# atmega_midi_x0x_heart_groundplane.net
KiCad netlist of a schematic drawn in EAGLE
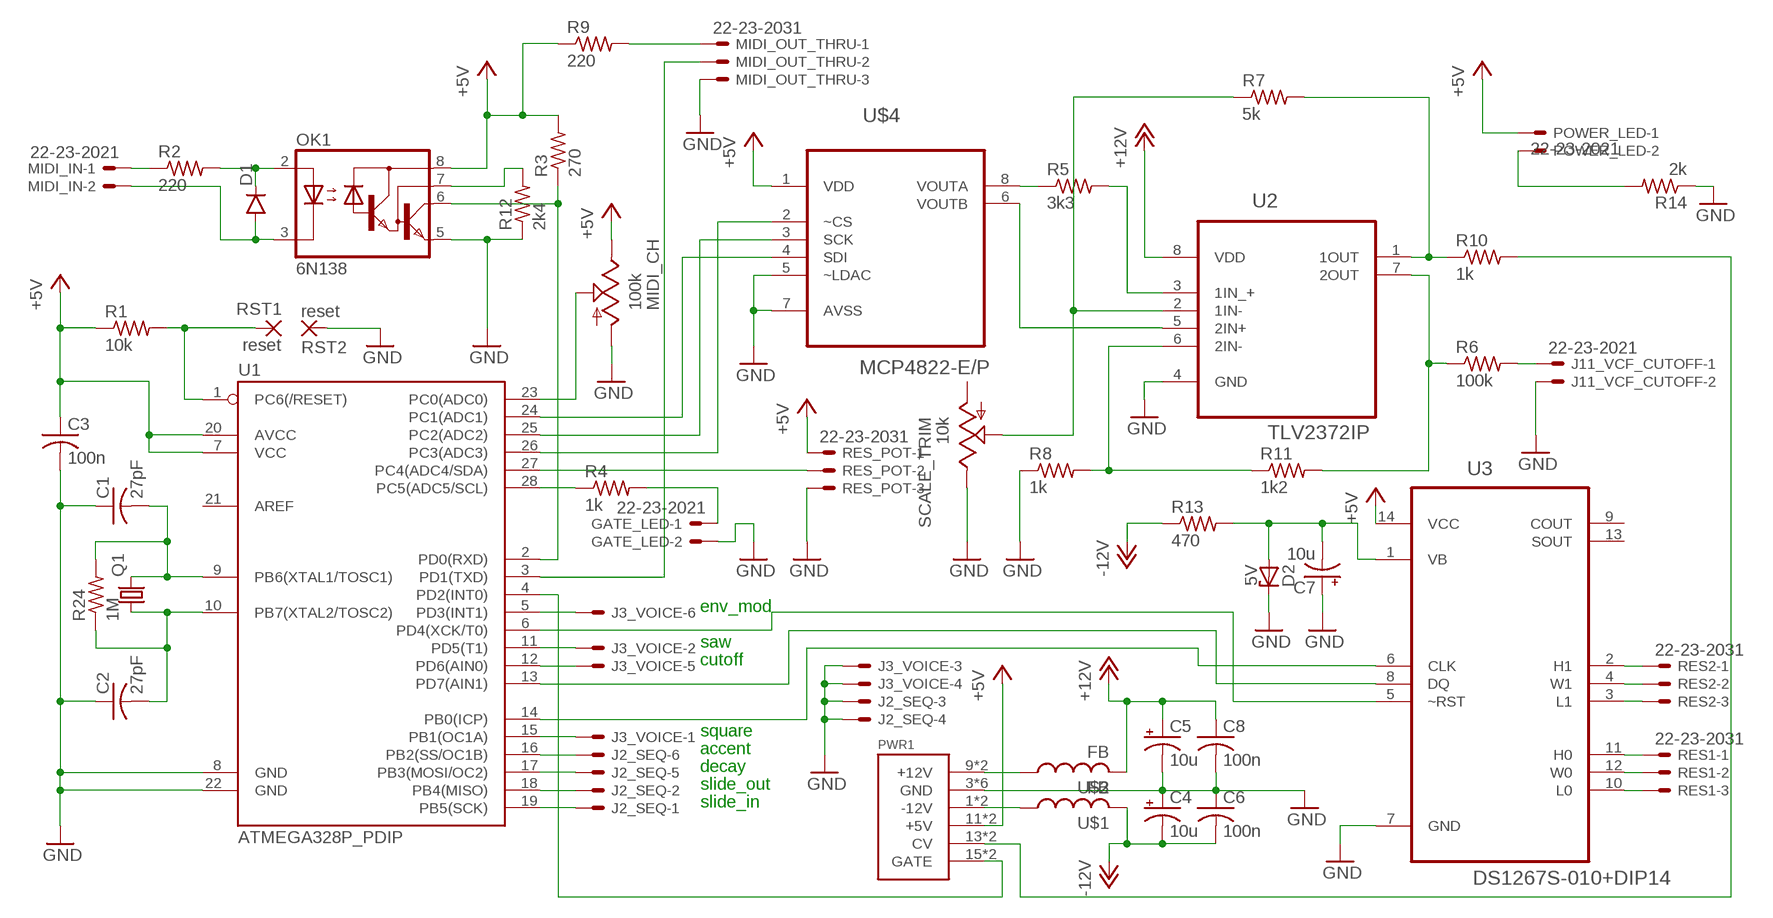
[diagram p0: schematic, sheet 1]

(export (version "E")
  (design (tool "Eeschema 10.0.6"))
  (components
    (comp (ref "C1")
      (value "27pF")
      (footprint "eagle-import:C050-024X044")
      (libsource (lib "eagle-import") (part "C-US050-024X044"))
    )
    (comp (ref "C2")
      (value "27pF")
      (footprint "eagle-import:C050-024X044")
      (libsource (lib "eagle-import") (part "C-US050-024X044"))
    )
    (comp (ref "C3")
      (value "100n")
      (footprint "eagle-import:C050-024X044")
      (libsource (lib "eagle-import") (part "C-US050-024X044"))
    )
    (comp (ref "C4")
      (value "10u")
      (footprint "eagle-import:B45181A")
      (libsource (lib "eagle-import") (part "CPOL-USB45181A"))
    )
    (comp (ref "C5")
      (value "10u")
      (footprint "eagle-import:B45181A")
      (libsource (lib "eagle-import") (part "CPOL-USB45181A"))
    )
    (comp (ref "C6")
      (value "100n")
      (footprint "eagle-import:C050-024X044")
      (libsource (lib "eagle-import") (part "C-US050-024X044"))
    )
    (comp (ref "C7")
      (value "10u")
      (footprint "eagle-import:B45181B")
      (libsource (lib "eagle-import") (part "CPOL-USB45181B"))
    )
    (comp (ref "C8")
      (value "100n")
      (footprint "eagle-import:C050-024X044")
      (libsource (lib "eagle-import") (part "C-US050-024X044"))
    )
    (comp (ref "D1")
      (value "DIODE1N4148")
      (footprint "eagle-import:DIODE-1N4148")
      (libsource (lib "eagle-import") (part "DIODE1N4148"))
    )
    (comp (ref "D2")
      (value "5V")
      (footprint "eagle-import:DO35Z10")
      (libsource (lib "eagle-import") (part "ZENER-DIODEDO35Z10"))
    )
    (comp (ref "GATE_LED")
      (value "22-23-2021")
      (footprint "eagle-import:22-23-2021")
      (fields (field (name "MF") "MOLEX"))
      (libsource (lib "eagle-import") (part "22-23-2021"))
    )
    (comp (ref "J2_SEQ")
      (value "22-23-2061")
      (footprint "eagle-import:22-23-2061")
      (fields (field (name "MF") "MOLEX"))
      (libsource (lib "eagle-import") (part "22-23-2061"))
    )
    (comp (ref "J3_VOICE")
      (value "22-23-2061")
      (footprint "eagle-import:22-23-2061")
      (fields (field (name "MF") "MOLEX"))
      (libsource (lib "eagle-import") (part "22-23-2061"))
    )
    (comp (ref "J11_VCF_CUTOFF")
      (value "22-23-2021")
      (footprint "eagle-import:22-23-2021")
      (fields (field (name "MF") "MOLEX"))
      (libsource (lib "eagle-import") (part "22-23-2021"))
    )
    (comp (ref "MIDI_CH")
      (value "100k")
      (footprint "eagle-import:B64W")
      (libsource (lib "eagle-import") (part "TRIM_US-B64W"))
    )
    (comp (ref "MIDI_IN")
      (value "22-23-2021")
      (footprint "eagle-import:22-23-2021")
      (fields (field (name "MF") "MOLEX"))
      (libsource (lib "eagle-import") (part "22-23-2021"))
    )
    (comp (ref "MIDI_OUT_THRU")
      (value "22-23-2031")
      (footprint "eagle-import:22-23-2031")
      (fields (field (name "MF") "MOLEX"))
      (libsource (lib "eagle-import") (part "22-23-2031"))
    )
    (comp (ref "OK1")
      (value "6N138")
      (footprint "eagle-import:DIL08")
      (fields (field (name "MF") "VISHAY/TELEFUNKEN"))
      (libsource (lib "eagle-import") (part "6N138"))
    )
    (comp (ref "POWER_LED")
      (value "22-23-2021")
      (footprint "eagle-import:22-23-2021")
      (fields (field (name "MF") "MOLEX"))
      (libsource (lib "eagle-import") (part "22-23-2021"))
    )
    (comp (ref "PWR1")
      (value "POWER")
      (footprint "eagle-import:POWER_16")
      (libsource (lib "eagle-import") (part "POWER"))
    )
    (comp (ref "Q1")
      (value "CRYSTALHC49S")
      (footprint "eagle-import:HC49_S")
      (libsource (lib "eagle-import") (part "CRYSTALHC49S"))
    )
    (comp (ref "R1")
      (value "10k")
      (footprint "eagle-import:0207_10")
      (libsource (lib "eagle-import") (part "R-US_0207/10"))
    )
    (comp (ref "R2")
      (value "220")
      (footprint "eagle-import:0207_10")
      (libsource (lib "eagle-import") (part "R-US_0207/10"))
    )
    (comp (ref "R3")
      (value "270")
      (footprint "eagle-import:0207_10")
      (libsource (lib "eagle-import") (part "R-US_0207/10"))
    )
    (comp (ref "R4")
      (value "1k")
      (footprint "eagle-import:0207_10")
      (libsource (lib "eagle-import") (part "R-US_0207/10"))
    )
    (comp (ref "R5")
      (value "3k3")
      (footprint "eagle-import:0207_10")
      (libsource (lib "eagle-import") (part "R-US_0207/10"))
    )
    (comp (ref "R6")
      (value "100k")
      (footprint "eagle-import:0207_10")
      (libsource (lib "eagle-import") (part "R-US_0207/10"))
    )
    (comp (ref "R7")
      (value "5k")
      (footprint "eagle-import:0207_10")
      (libsource (lib "eagle-import") (part "R-US_0207/10"))
    )
    (comp (ref "R8")
      (value "1k")
      (footprint "eagle-import:0207_10")
      (libsource (lib "eagle-import") (part "R-US_0207/10"))
    )
    (comp (ref "R9")
      (value "220")
      (footprint "eagle-import:0207_10")
      (libsource (lib "eagle-import") (part "R-US_0207/10"))
    )
    (comp (ref "R10")
      (value "1k")
      (footprint "eagle-import:0207_10")
      (libsource (lib "eagle-import") (part "R-US_0207/10"))
    )
    (comp (ref "R11")
      (value "1k2")
      (footprint "eagle-import:0207_10")
      (libsource (lib "eagle-import") (part "R-US_0207/10"))
    )
    (comp (ref "R12")
      (value "2k4")
      (footprint "eagle-import:0207_10")
      (libsource (lib "eagle-import") (part "R-US_0207/10"))
    )
    (comp (ref "R13")
      (value "470")
      (footprint "eagle-import:0207_10")
      (libsource (lib "eagle-import") (part "R-US_0207/10"))
    )
    (comp (ref "R14")
      (value "2k")
      (footprint "eagle-import:0207_10")
      (libsource (lib "eagle-import") (part "R-US_0207/10"))
    )
    (comp (ref "R24")
      (value "1M")
      (footprint "eagle-import:0207_10")
      (libsource (lib "eagle-import") (part "R-US_0207/10"))
    )
    (comp (ref "RES1")
      (value "22-23-2031")
      (footprint "eagle-import:22-23-2031")
      (fields (field (name "MF") "MOLEX"))
      (libsource (lib "eagle-import") (part "22-23-2031"))
    )
    (comp (ref "RES2")
      (value "22-23-2031")
      (footprint "eagle-import:22-23-2031")
      (fields (field (name "MF") "MOLEX"))
      (libsource (lib "eagle-import") (part "22-23-2031"))
    )
    (comp (ref "RES_POT")
      (value "22-23-2031")
      (footprint "eagle-import:22-23-2031")
      (fields (field (name "MF") "MOLEX"))
      (libsource (lib "eagle-import") (part "22-23-2031"))
    )
    (comp (ref "RST1")
      (value "reset")
      (footprint "eagle-import:2,54_0,9")
      (libsource (lib "eagle-import") (part "2,54/0,9"))
    )
    (comp (ref "RST2")
      (value "reset")
      (footprint "eagle-import:2,54_0,9")
      (libsource (lib "eagle-import") (part "2,54/0,9"))
    )
    (comp (ref "SCALE_TRIM")
      (value "10k")
      (footprint "eagle-import:B64W")
      (libsource (lib "eagle-import") (part "TRIM_US-B64W"))
    )
    (comp (ref "U$1") (value "FB") (footprint "eagle-import:FB") (libsource (lib "eagle-import") (part "FB")))
    (comp (ref "U$2") (value "FB") (footprint "eagle-import:FB") (libsource (lib "eagle-import") (part "FB")))
    (comp (ref "U$4")
      (value "MCP4822-E/P")
      (footprint "eagle-import:DIP254P762X432-8")
      (libsource (lib "eagle-import") (part "MCP4822-E/P"))
    )
    (comp (ref "U1")
      (value "ATMEGA328P_PDIP")
      (footprint "eagle-import:DIL28-3")
      (libsource (lib "eagle-import") (part "ATMEGA328P_PDIP"))
    )
    (comp (ref "U2")
      (value "TLV2372IP")
      (footprint "eagle-import:DIP254P762X508-8")
      (libsource (lib "eagle-import") (part "TLV2372IP"))
    )
    (comp (ref "U3")
      (value "DS1267S-010+DIP14")
      (footprint "eagle-import:DIP14")
      (libsource (lib "eagle-import") (part "DS1267S-010+DIP14"))
    )
  )
  (nets
    (net (code "1") (name "+5V") (class "Default")
      (node (ref "C3") (pin "1") (pinfunction "1_1") (pintype "passive"))
      (node (ref "MIDI_CH") (pin "E") (pinfunction "E_E") (pintype "passive"))
      (node (ref "OK1") (pin "8") (pinfunction "VCC_8") (pintype "passive"))
      (node (ref "POWER_LED") (pin "1") (pinfunction "S_1") (pintype "passive"))
      (node (ref "PWR1") (pin "11") (pinfunction "+5V_11") (pintype "bidirectional"))
      (node (ref "PWR1") (pin "12") (pinfunction "+5V_12") (pintype "bidirectional"))
      (node (ref "R1") (pin "1") (pinfunction "1_1") (pintype "passive"))
      (node (ref "R3") (pin "2") (pinfunction "2_2") (pintype "passive"))
      (node (ref "R9") (pin "1") (pinfunction "1_1") (pintype "passive"))
      (node (ref "RES_POT") (pin "1") (pinfunction "S_1") (pintype "passive"))
      (node (ref "U$4") (pin "1") (pinfunction "VDD_1") (pintype "power_in"))
      (node (ref "U1") (pin "20") (pinfunction "AVCC_20") (pintype "bidirectional"))
      (node (ref "U1") (pin "7") (pinfunction "VCC_7") (pintype "bidirectional"))
      (node (ref "U3") (pin "14") (pinfunction "VCC_14") (pintype "power_in"))
    )
    (net (code "2") (name "+12V") (class "Default")
      (node (ref "C5") (pin "+") (pinfunction "+_+") (pintype "passive"))
      (node (ref "C8") (pin "1") (pinfunction "1_1") (pintype "passive"))
      (node (ref "U$2") (pin "P$2") (pinfunction "2_P$2") (pintype "passive"))
      (node (ref "U2") (pin "8") (pinfunction "VDD_8") (pintype "power_in"))
    )
    (net (code "3") (name "-12V") (class "Default")
      (node (ref "C4") (pin "-") (pinfunction "-_-") (pintype "passive"))
      (node (ref "C6") (pin "2") (pinfunction "2_2") (pintype "passive"))
      (node (ref "R13") (pin "1") (pinfunction "1_1") (pintype "passive"))
      (node (ref "U$1") (pin "P$2") (pinfunction "2_P$2") (pintype "passive"))
    )
    (net (code "4") (name "GND") (class "Default")
      (node (ref "C1") (pin "1") (pinfunction "1_1") (pintype "passive"))
      (node (ref "C2") (pin "1") (pinfunction "1_1") (pintype "passive"))
      (node (ref "C3") (pin "2") (pinfunction "2_2") (pintype "passive"))
      (node (ref "C4") (pin "+") (pinfunction "+_+") (pintype "passive"))
      (node (ref "C5") (pin "-") (pinfunction "-_-") (pintype "passive"))
      (node (ref "C6") (pin "1") (pinfunction "1_1") (pintype "passive"))
      (node (ref "C7") (pin "+") (pinfunction "+_+") (pintype "passive"))
      (node (ref "C8") (pin "2") (pinfunction "2_2") (pintype "passive"))
      (node (ref "D2") (pin "C") (pinfunction "C_C") (pintype "passive"))
      (node (ref "GATE_LED") (pin "2") (pinfunction "S_2") (pintype "passive"))
      (node (ref "J11_VCF_CUTOFF") (pin "2") (pinfunction "S_2") (pintype "passive"))
      (node (ref "J2_SEQ") (pin "3") (pinfunction "S_3") (pintype "passive"))
      (node (ref "J2_SEQ") (pin "4") (pinfunction "S_4") (pintype "passive"))
      (node (ref "J3_VOICE") (pin "3") (pinfunction "S_3") (pintype "passive"))
      (node (ref "J3_VOICE") (pin "4") (pinfunction "S_4") (pintype "passive"))
      (node (ref "MIDI_CH") (pin "A") (pinfunction "A_A") (pintype "passive"))
      (node (ref "MIDI_OUT_THRU") (pin "3") (pinfunction "S_3") (pintype "passive"))
      (node (ref "OK1") (pin "5") (pinfunction "GND_5") (pintype "passive"))
      (node (ref "PWR1") (pin "3") (pinfunction "GND_3") (pintype "bidirectional"))
      (node (ref "PWR1") (pin "4") (pinfunction "GND_4") (pintype "bidirectional"))
      (node (ref "PWR1") (pin "5") (pinfunction "GND_5") (pintype "bidirectional"))
      (node (ref "PWR1") (pin "6") (pinfunction "GND_6") (pintype "bidirectional"))
      (node (ref "PWR1") (pin "7") (pinfunction "GND_7") (pintype "bidirectional"))
      (node (ref "PWR1") (pin "8") (pinfunction "GND_8") (pintype "bidirectional"))
      (node (ref "R12") (pin "1") (pinfunction "1_1") (pintype "passive"))
      (node (ref "R14") (pin "1") (pinfunction "1_1") (pintype "passive"))
      (node (ref "R8") (pin "1") (pinfunction "1_1") (pintype "passive"))
      (node (ref "RES_POT") (pin "3") (pinfunction "S_3") (pintype "passive"))
      (node (ref "RST2") (pin "1") (pinfunction "P_1") (pintype "passive"))
      (node (ref "SCALE_TRIM") (pin "E") (pinfunction "E_E") (pintype "passive"))
      (node (ref "U$4") (pin "5") (pinfunction "~{LDAC}_5") (pintype "input"))
      (node (ref "U$4") (pin "7") (pinfunction "AVSS_7") (pintype "passive"))
      (node (ref "U1") (pin "22") (pinfunction "GND_22") (pintype "bidirectional"))
      (node (ref "U1") (pin "8") (pinfunction "GND_8") (pintype "bidirectional"))
      (node (ref "U2") (pin "4") (pinfunction "GND_4") (pintype "passive"))
      (node (ref "U3") (pin "7") (pinfunction "GND_7") (pintype "passive"))
    )
    (net (code "5") (name "Net-(GATE_LEDA-S)") (class "Default")
      (node (ref "GATE_LED") (pin "1") (pinfunction "S_1") (pintype "passive"))
      (node (ref "R4") (pin "2") (pinfunction "2_2") (pintype "passive"))
    )
    (net (code "6") (name "Net-(J2_SEQA-S)") (class "Default")
      (node (ref "J2_SEQ") (pin "1") (pinfunction "S_1") (pintype "passive"))
      (node (ref "U1") (pin "19") (pinfunction "PB5(SCK)_19") (pintype "bidirectional"))
    )
    (net (code "7") (name "Net-(J2_SEQB-S)") (class "Default")
      (node (ref "J2_SEQ") (pin "2") (pinfunction "S_2") (pintype "passive"))
      (node (ref "U1") (pin "18") (pinfunction "PB4(MISO)_18") (pintype "bidirectional"))
    )
    (net (code "8") (name "Net-(J2_SEQE-S)") (class "Default")
      (node (ref "J2_SEQ") (pin "5") (pinfunction "S_5") (pintype "passive"))
      (node (ref "U1") (pin "17") (pinfunction "PB3(MOSI/OC2)_17") (pintype "bidirectional"))
    )
    (net (code "9") (name "Net-(J2_SEQF-S)") (class "Default")
      (node (ref "J2_SEQ") (pin "6") (pinfunction "S_6") (pintype "passive"))
      (node (ref "U1") (pin "16") (pinfunction "PB2(SS/OC1B)_16") (pintype "bidirectional"))
    )
    (net (code "10") (name "Net-(J3_VOICEA-S)") (class "Default")
      (node (ref "J3_VOICE") (pin "1") (pinfunction "S_1") (pintype "passive"))
      (node (ref "U1") (pin "15") (pinfunction "PB1(OC1A)_15") (pintype "bidirectional"))
    )
    (net (code "11") (name "Net-(J3_VOICEB-S)") (class "Default")
      (node (ref "J3_VOICE") (pin "2") (pinfunction "S_2") (pintype "passive"))
      (node (ref "U1") (pin "11") (pinfunction "PD5(T1)_11") (pintype "bidirectional"))
    )
    (net (code "12") (name "Net-(J3_VOICEE-S)") (class "Default")
      (node (ref "J3_VOICE") (pin "5") (pinfunction "S_5") (pintype "passive"))
      (node (ref "U1") (pin "12") (pinfunction "PD6(AIN0)_12") (pintype "bidirectional"))
    )
    (net (code "13") (name "Net-(J3_VOICEF-S)") (class "Default")
      (node (ref "J3_VOICE") (pin "6") (pinfunction "S_6") (pintype "passive"))
      (node (ref "U1") (pin "5") (pinfunction "PD3(INT1)_5") (pintype "bidirectional"))
    )
    (net (code "14") (name "Net-(J11_VCF_CUTOFFA-S)") (class "Default")
      (node (ref "J11_VCF_CUTOFF") (pin "1") (pinfunction "S_1") (pintype "passive"))
      (node (ref "R6") (pin "2") (pinfunction "2_2") (pintype "passive"))
    )
    (net (code "15") (name "Net-(MIDI_INA-S)") (class "Default")
      (node (ref "MIDI_IN") (pin "1") (pinfunction "S_1") (pintype "passive"))
      (node (ref "R2") (pin "1") (pinfunction "1_1") (pintype "passive"))
    )
    (net (code "16") (name "Net-(MIDI_INB-S)") (class "Default")
      (node (ref "D1") (pin "A") (pinfunction "A_A") (pintype "passive"))
      (node (ref "MIDI_IN") (pin "2") (pinfunction "S_2") (pintype "passive"))
      (node (ref "OK1") (pin "3") (pinfunction "C_3") (pintype "passive"))
    )
    (net (code "17") (name "Net-(MIDI_OUT_THRUA-S)") (class "Default")
      (node (ref "MIDI_OUT_THRU") (pin "1") (pinfunction "S_1") (pintype "passive"))
      (node (ref "R9") (pin "2") (pinfunction "2_2") (pintype "passive"))
    )
    (net (code "18") (name "Net-(MIDI_OUT_THRUB-S)") (class "Default")
      (node (ref "MIDI_OUT_THRU") (pin "2") (pinfunction "S_2") (pintype "passive"))
      (node (ref "U1") (pin "3") (pinfunction "PD1(TXD)_3") (pintype "bidirectional"))
    )
    (net (code "19") (name "Net-(OK1-A)") (class "Default")
      (node (ref "D1") (pin "C") (pinfunction "C_C") (pintype "passive"))
      (node (ref "OK1") (pin "2") (pinfunction "A_2") (pintype "passive"))
      (node (ref "R2") (pin "2") (pinfunction "2_2") (pintype "passive"))
    )
    (net (code "20") (name "Net-(OK1-VB)") (class "Default")
      (node (ref "OK1") (pin "7") (pinfunction "VB_7") (pintype "passive"))
      (node (ref "R12") (pin "2") (pinfunction "2_2") (pintype "passive"))
    )
    (net (code "21") (name "Net-(OK1-VO)") (class "Default")
      (node (ref "OK1") (pin "6") (pinfunction "VO_6") (pintype "passive"))
      (node (ref "R3") (pin "1") (pinfunction "1_1") (pintype "passive"))
      (node (ref "U1") (pin "2") (pinfunction "PD0(RXD)_2") (pintype "bidirectional"))
    )
    (net (code "22") (name "Net-(POWER_LEDB-S)") (class "Default")
      (node (ref "POWER_LED") (pin "2") (pinfunction "S_2") (pintype "passive"))
      (node (ref "R14") (pin "2") (pinfunction "2_2") (pintype "passive"))
    )
    (net (code "23") (name "Net-(PWR1-CV-Pad13)") (class "Default")
      (node (ref "PWR1") (pin "13") (pinfunction "CV_13") (pintype "bidirectional"))
      (node (ref "PWR1") (pin "14") (pinfunction "CV_14") (pintype "bidirectional"))
      (node (ref "R10") (pin "2") (pinfunction "2_2") (pintype "passive"))
    )
    (net (code "24") (name "Net-(RES1A-S)") (class "Default")
      (node (ref "RES1") (pin "1") (pinfunction "S_1") (pintype "passive"))
      (node (ref "U3") (pin "11") (pinfunction "H0_11") (pintype "passive"))
    )
    (net (code "25") (name "Net-(RES1B-S)") (class "Default")
      (node (ref "RES1") (pin "2") (pinfunction "S_2") (pintype "passive"))
      (node (ref "U3") (pin "12") (pinfunction "W0_12") (pintype "passive"))
    )
    (net (code "26") (name "Net-(RES1C-S)") (class "Default")
      (node (ref "RES1") (pin "3") (pinfunction "S_3") (pintype "passive"))
      (node (ref "U3") (pin "10") (pinfunction "L0_10") (pintype "passive"))
    )
    (net (code "27") (name "Net-(RES2A-S)") (class "Default")
      (node (ref "RES2") (pin "1") (pinfunction "S_1") (pintype "passive"))
      (node (ref "U3") (pin "2") (pinfunction "H1_2") (pintype "passive"))
    )
    (net (code "28") (name "Net-(RES2B-S)") (class "Default")
      (node (ref "RES2") (pin "2") (pinfunction "S_2") (pintype "passive"))
      (node (ref "U3") (pin "4") (pinfunction "W1_4") (pintype "passive"))
    )
    (net (code "29") (name "Net-(RES2C-S)") (class "Default")
      (node (ref "RES2") (pin "3") (pinfunction "S_3") (pintype "passive"))
      (node (ref "U3") (pin "3") (pinfunction "L1_3") (pintype "passive"))
    )
    (net (code "30") (name "Net-(RES_POTB-S)") (class "Default")
      (node (ref "RES_POT") (pin "2") (pinfunction "S_2") (pintype "passive"))
      (node (ref "U1") (pin "27") (pinfunction "PC4(ADC4/SDA)_27") (pintype "bidirectional"))
    )
    (net (code "31") (name "Net-(RST1-P)") (class "Default")
      (node (ref "R1") (pin "2") (pinfunction "2_2") (pintype "passive"))
      (node (ref "RST1") (pin "1") (pinfunction "P_1") (pintype "passive"))
      (node (ref "U1") (pin "1") (pinfunction "PC6(/RESET)_1") (pintype "bidirectional"))
    )
    (net (code "32") (name "Net-(U$1-1)") (class "Default")
      (node (ref "PWR1") (pin "1") (pinfunction "-12V_1") (pintype "bidirectional"))
      (node (ref "PWR1") (pin "2") (pinfunction "-12V_2") (pintype "bidirectional"))
      (node (ref "U$1") (pin "P$1") (pinfunction "1_P$1") (pintype "passive"))
    )
    (net (code "33") (name "Net-(U$2-1)") (class "Default")
      (node (ref "PWR1") (pin "10") (pinfunction "+12V_10") (pintype "bidirectional"))
      (node (ref "PWR1") (pin "9") (pinfunction "+12V_9") (pintype "bidirectional"))
      (node (ref "U$2") (pin "P$1") (pinfunction "1_P$1") (pintype "passive"))
    )
    (net (code "34") (name "Net-(U$4-SCK)") (class "Default")
      (node (ref "U$4") (pin "3") (pinfunction "SCK_3") (pintype "input"))
      (node (ref "U1") (pin "25") (pinfunction "PC2(ADC2)_25") (pintype "bidirectional"))
    )
    (net (code "35") (name "Net-(U$4-SDI)") (class "Default")
      (node (ref "U$4") (pin "4") (pinfunction "SDI_4") (pintype "input"))
      (node (ref "U1") (pin "24") (pinfunction "PC1(ADC1)_24") (pintype "bidirectional"))
    )
    (net (code "36") (name "Net-(U$4-VOUTA)") (class "Default")
      (node (ref "R5") (pin "1") (pinfunction "1_1") (pintype "passive"))
      (node (ref "U$4") (pin "8") (pinfunction "VOUTA_8") (pintype "output"))
    )
    (net (code "37") (name "Net-(U$4-VOUTB)") (class "Default")
      (node (ref "U$4") (pin "6") (pinfunction "VOUTB_6") (pintype "output"))
      (node (ref "U2") (pin "5") (pinfunction "2IN+_5") (pintype "input"))
    )
    (net (code "38") (name "Net-(U$4-~{CS})") (class "Default")
      (node (ref "U$4") (pin "2") (pinfunction "~{CS}_2") (pintype "input"))
      (node (ref "U1") (pin "26") (pinfunction "PC3(ADC3)_26") (pintype "bidirectional"))
    )
    (net (code "39") (name "Net-(U1-PB0(ICP))") (class "Default")
      (node (ref "U1") (pin "14") (pinfunction "PB0(ICP)_14") (pintype "bidirectional"))
      (node (ref "U3") (pin "6") (pinfunction "CLK_6") (pintype "input"))
    )
    (net (code "40") (name "Net-(U1-PB6(XTAL1{slash}TOSC1))") (class "Default")
      (node (ref "C1") (pin "2") (pinfunction "2_2") (pintype "passive"))
      (node (ref "Q1") (pin "2") (pinfunction "2_2") (pintype "passive"))
      (node (ref "R24") (pin "2") (pinfunction "2_2") (pintype "passive"))
      (node (ref "U1") (pin "9") (pinfunction "PB6(XTAL1/TOSC1)_9") (pintype "bidirectional"))
    )
    (net (code "41") (name "Net-(U1-PB7(XTAL2{slash}TOSC2))") (class "Default")
      (node (ref "C2") (pin "2") (pinfunction "2_2") (pintype "passive"))
      (node (ref "Q1") (pin "1") (pinfunction "1_1") (pintype "passive"))
      (node (ref "R24") (pin "1") (pinfunction "1_1") (pintype "passive"))
      (node (ref "U1") (pin "10") (pinfunction "PB7(XTAL2/TOSC2)_10") (pintype "bidirectional"))
    )
    (net (code "42") (name "Net-(U1-PC0(ADC0))") (class "Default")
      (node (ref "MIDI_CH") (pin "S") (pinfunction "S_S") (pintype "passive"))
      (node (ref "U1") (pin "23") (pinfunction "PC0(ADC0)_23") (pintype "bidirectional"))
    )
    (net (code "43") (name "Net-(U1-PC5(ADC5{slash}SCL))") (class "Default")
      (node (ref "R4") (pin "1") (pinfunction "1_1") (pintype "passive"))
      (node (ref "U1") (pin "28") (pinfunction "PC5(ADC5/SCL)_28") (pintype "bidirectional"))
    )
    (net (code "44") (name "Net-(U1-PD2(INT0))") (class "Default")
      (node (ref "PWR1") (pin "15") (pinfunction "GATE_15") (pintype "bidirectional"))
      (node (ref "PWR1") (pin "16") (pinfunction "GATE_16") (pintype "bidirectional"))
      (node (ref "U1") (pin "4") (pinfunction "PD2(INT0)_4") (pintype "bidirectional"))
    )
    (net (code "45") (name "Net-(U1-PD4(XCK{slash}T0))") (class "Default")
      (node (ref "U1") (pin "6") (pinfunction "PD4(XCK/T0)_6") (pintype "bidirectional"))
      (node (ref "U3") (pin "5") (pinfunction "~{RST}_5") (pintype "input"))
    )
    (net (code "46") (name "Net-(U1-PD7(AIN1))") (class "Default")
      (node (ref "U1") (pin "13") (pinfunction "PD7(AIN1)_13") (pintype "bidirectional"))
      (node (ref "U3") (pin "8") (pinfunction "DQ_8") (pintype "input"))
    )
    (net (code "47") (name "Net-(U2-1IN-)") (class "Default")
      (node (ref "R7") (pin "1") (pinfunction "1_1") (pintype "passive"))
      (node (ref "SCALE_TRIM") (pin "S") (pinfunction "S_S") (pintype "passive"))
      (node (ref "U2") (pin "2") (pinfunction "1IN-_2") (pintype "input"))
    )
    (net (code "48") (name "Net-(U2-1IN_+)") (class "Default")
      (node (ref "R5") (pin "2") (pinfunction "2_2") (pintype "passive"))
      (node (ref "U2") (pin "3") (pinfunction "1IN_+_3") (pintype "input"))
    )
    (net (code "49") (name "Net-(U2-1OUT)") (class "Default")
      (node (ref "R10") (pin "1") (pinfunction "1_1") (pintype "passive"))
      (node (ref "R7") (pin "2") (pinfunction "2_2") (pintype "passive"))
      (node (ref "U2") (pin "1") (pinfunction "1OUT_1") (pintype "output"))
    )
    (net (code "50") (name "Net-(U2-2IN-)") (class "Default")
      (node (ref "R11") (pin "1") (pinfunction "1_1") (pintype "passive"))
      (node (ref "R8") (pin "2") (pinfunction "2_2") (pintype "passive"))
      (node (ref "U2") (pin "6") (pinfunction "2IN-_6") (pintype "input"))
    )
    (net (code "51") (name "Net-(U2-2OUT)") (class "Default")
      (node (ref "R11") (pin "2") (pinfunction "2_2") (pintype "passive"))
      (node (ref "R6") (pin "1") (pinfunction "1_1") (pintype "passive"))
      (node (ref "U2") (pin "7") (pinfunction "2OUT_7") (pintype "output"))
    )
    (net (code "52") (name "Net-(U3-VB)") (class "Default")
      (node (ref "C7") (pin "-") (pinfunction "-_-") (pintype "passive"))
      (node (ref "D2") (pin "A") (pinfunction "A_A") (pintype "passive"))
      (node (ref "R13") (pin "2") (pinfunction "2_2") (pintype "passive"))
      (node (ref "U3") (pin "1") (pinfunction "VB_1") (pintype "input"))
    )
    (net (code "53") (name "unconnected-(SCALE_TRIM-PadA)") (class "Default")
      (node (ref "SCALE_TRIM") (pin "A") (pinfunction "A_A") (pintype "passive"))
    )
    (net (code "54") (name "unconnected-(U1-AREF-Pad21)") (class "Default")
      (node (ref "U1") (pin "21") (pinfunction "AREF_21") (pintype "bidirectional"))
    )
    (net (code "55") (name "unconnected-(U3-COUT-Pad9)") (class "Default")
      (node (ref "U3") (pin "9") (pinfunction "COUT_9") (pintype "output"))
    )
    (net (code "56") (name "unconnected-(U3-SOUT-Pad13)") (class "Default")
      (node (ref "U3") (pin "13") (pinfunction "SOUT_13") (pintype "output"))
    )
  )
)
